# TemperatureSensor.net
KiCad netlist of a schematic drawn in Altium Designer
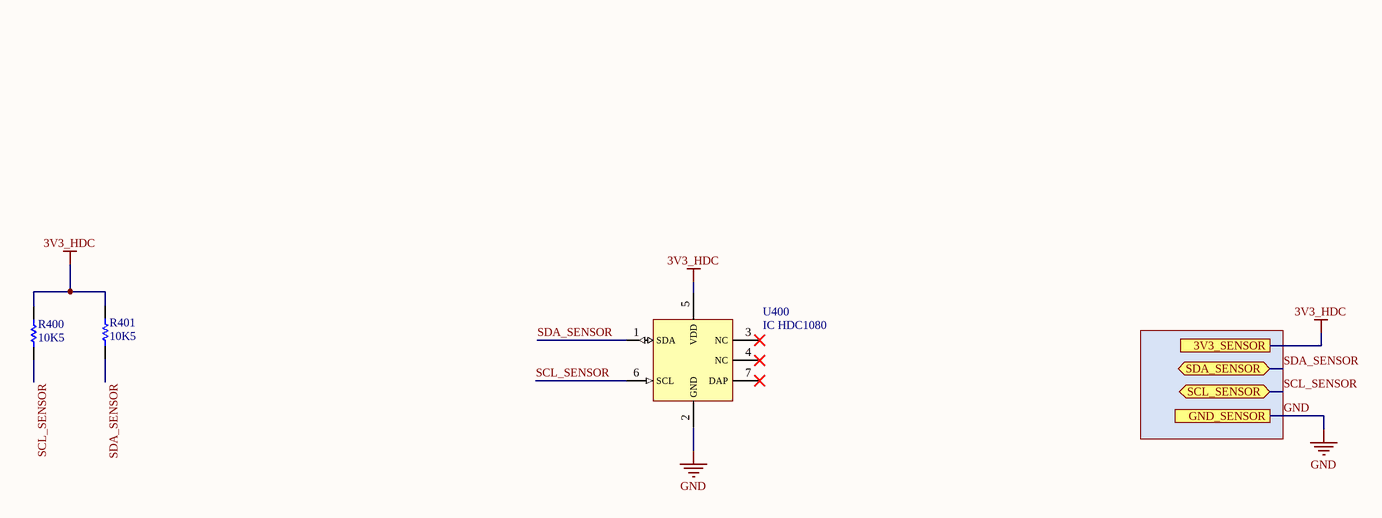
[diagram p0: TemperatureSensor.SchDoc]

(export (version "E")
  (design (tool "Eeschema 10.0.6"))
  (components
    (comp (ref "R400")
      (value "10K5")
      (footprint "CR2012-0805")
      (description "RES SMD 10.5K OHM 0.1% 1/8W 0805")
      (fields
        (field (name "TOLERANCE") "±0.1%")
        (field (name "MANUFACTURER") "Panasonic Electronic Components")
        (field (name "SOURCE") "mits.SchLib")
      )
      (libsource (lib "Mobit Brasil Ltda") (part "Symbol"))
    )
    (comp (ref "R401")
      (value "10K5")
      (footprint "CR2012-0805")
      (description "RES SMD 10.5K OHM 0.1% 1/8W 0805")
      (fields
        (field (name "TOLERANCE") "±0.1%")
        (field (name "MANUFACTURER") "Panasonic Electronic Components")
        (field (name "SOURCE") "mits.SchLib")
      )
      (libsource (lib "Mobit Brasil Ltda") (part "Symbol"))
    )
    (comp (ref "U400")
      (value "IC HDC1080")
      (footprint "PSON100P300X80_HS-7N")
      (description "SENSOR HUMI/TEMP 3.3V I2C 4% SMD")
      (fields (field (name "SOURCE") "mits.SchLib"))
      (libsource (lib "Mobit Brasil Ltda") (part "IC HDC1080 TEMP/HUMID SENSOR 6-PWSON"))
    )
  )
  (nets
    (net (code "1") (name "/SCL_SENSOR") (class "Default")
      (node (ref "R400") (pin "1") (pinfunction "1_1") (pintype "passive"))
      (node (ref "U400") (pin "6") (pinfunction "SCL_6") (pintype "input"))
    )
    (net (code "2") (name "/SDA_SENSOR") (class "Default")
      (node (ref "R401") (pin "1") (pinfunction "1_1") (pintype "passive"))
      (node (ref "U400") (pin "1") (pinfunction "SDA_1") (pintype "bidirectional"))
    )
    (net (code "3") (name "3V3_HDC") (class "Default")
      (node (ref "R400") (pin "2") (pinfunction "2_2") (pintype "passive"))
      (node (ref "R401") (pin "2") (pinfunction "2_2") (pintype "passive"))
      (node (ref "U400") (pin "5") (pinfunction "VDD_5") (pintype "passive"))
    )
    (net (code "4") (name "GND") (class "Default")
      (node (ref "U400") (pin "2") (pinfunction "GND_2") (pintype "passive"))
    )
    (net (code "5") (name "unconnected-(U400-DAP-Pad7)") (class "Default")
      (node (ref "U400") (pin "7") (pinfunction "DAP_7") (pintype "passive+no_connect"))
    )
    (net (code "6") (name "unconnected-(U400-NC-Pad3)") (class "Default")
      (node (ref "U400") (pin "3") (pinfunction "NC_3") (pintype "passive+no_connect"))
    )
    (net (code "7") (name "unconnected-(U400-NC-Pad4)") (class "Default")
      (node (ref "U400") (pin "4") (pinfunction "NC_4") (pintype "passive+no_connect"))
    )
  )
)
